# FirebeetleNodoFinal.net
KiCad netlist of a schematic drawn in Altium Designer
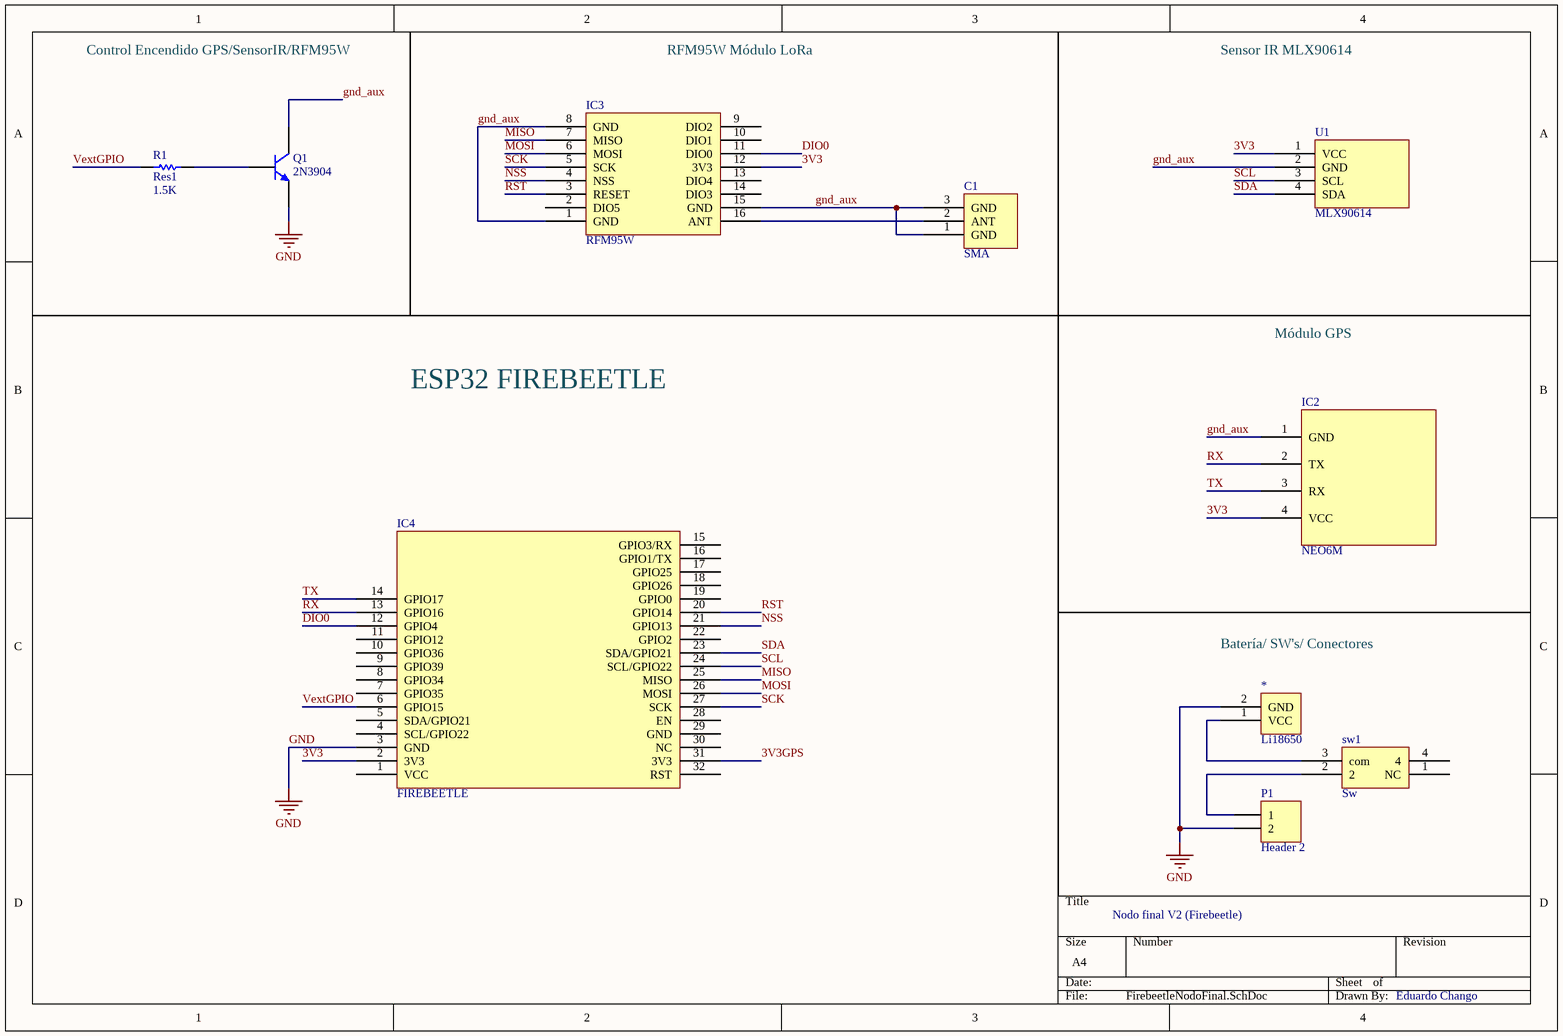
[diagram p0: FirebeetleNodoFinal.SchDoc]

(export (version "E")
  (design (tool "Eeschema 10.0.6"))
  (components
    (comp (ref "*")
      (value "Li18650")
      (footprint "Li18650")
      (libsource (lib "ComponentesTesis") (part "Li18650"))
    )
    (comp (ref "C1") (value "SMA") (footprint "SMA") (libsource (lib "ComponentesTesis") (part "SMA")))
    (comp (ref "IC2")
      (value "NEO6M")
      (footprint "NEO6M")
      (description "GPS NEO6M")
      (libsource (lib "ComponentesTesis") (part "NEO6M"))
    )
    (comp (ref "IC3")
      (value "RFM95W")
      (footprint "RFM95W")
      (libsource (lib "ComponentesTesis") (part "RFM95W"))
    )
    (comp (ref "IC4")
      (value "FIREBEETLE")
      (footprint "FIREBEETLE")
      (libsource (lib "ComponentesTesis") (part "FIREBEETLE"))
    )
    (comp (ref "P1")
      (value "Header 2")
      (footprint "HDR1X2")
      (description "Header, 2-Pin")
      (fields (field (name "PUBLISHER") "Altium Limited"))
      (libsource (lib "Miscellaneous Connectors") (part "Header 2"))
    )
    (comp (ref "Q1")
      (value "2N3904")
      (footprint "TO-92A")
      (description "NPN General Purpose Amplifier")
      (fields (field (name "PUBLISHER") "Altium Limited"))
      (libsource (lib "Miscellaneous Devices") (part "2N3904"))
    )
    (comp (ref "R1")
      (value "Res1")
      (footprint "AXIAL-0.3")
      (description "Resistor")
      (fields (field (name "ALTIUM_VALUE") "1.5K") (field (name "PUBLISHER") "Altium Limited"))
      (libsource (lib "Miscellaneous Devices") (part "Res1"))
    )
    (comp (ref "sw1")
      (value "Sw")
      (footprint "InterruptorSMD")
      (libsource (lib "ComponentesTesis") (part "Sw"))
    )
    (comp (ref "U1")
      (value "MLX90614")
      (footprint "IRSENSOR")
      (description "iR SENSOR TEMPERATURA")
      (libsource (lib "ComponentesTesis") (part "MLX90614"))
    )
  )
  (nets
    (net (code "1") (name "/3V3") (class "Default")
      (node (ref "IC2") (pin "4") (pinfunction "VCC_4") (pintype "passive"))
      (node (ref "IC3") (pin "12") (pinfunction "3V3_12") (pintype "power_in"))
      (node (ref "IC4") (pin "2") (pinfunction "3V3_2") (pintype "power_in"))
      (node (ref "U1") (pin "1") (pinfunction "VCC_1") (pintype "power_in"))
    )
    (net (code "2") (name "/3V3GPS") (class "Default")
      (node (ref "IC4") (pin "31") (pinfunction "3V3_31") (pintype "power_in"))
    )
    (net (code "3") (name "/DIO0") (class "Default")
      (node (ref "IC3") (pin "11") (pinfunction "DIO0_11") (pintype "passive"))
      (node (ref "IC4") (pin "12") (pinfunction "GPIO4_12") (pintype "power_in"))
    )
    (net (code "4") (name "/MISO") (class "Default")
      (node (ref "IC3") (pin "7") (pinfunction "MISO_7") (pintype "passive"))
      (node (ref "IC4") (pin "25") (pinfunction "MISO_25") (pintype "power_in"))
    )
    (net (code "5") (name "/MOSI") (class "Default")
      (node (ref "IC3") (pin "6") (pinfunction "MOSI_6") (pintype "passive"))
      (node (ref "IC4") (pin "26") (pinfunction "MOSI_26") (pintype "power_in"))
    )
    (net (code "6") (name "/NSS") (class "Default")
      (node (ref "IC3") (pin "4") (pinfunction "NSS_4") (pintype "passive"))
      (node (ref "IC4") (pin "21") (pinfunction "GPIO13_21") (pintype "power_in"))
    )
    (net (code "7") (name "/RST") (class "Default")
      (node (ref "IC3") (pin "3") (pinfunction "RESET_3") (pintype "passive"))
      (node (ref "IC4") (pin "20") (pinfunction "GPIO14_20") (pintype "power_in"))
    )
    (net (code "8") (name "/RX") (class "Default")
      (node (ref "IC2") (pin "2") (pinfunction "TX_2") (pintype "passive"))
      (node (ref "IC4") (pin "13") (pinfunction "GPIO16_13") (pintype "power_in"))
    )
    (net (code "9") (name "/SCK") (class "Default")
      (node (ref "IC3") (pin "5") (pinfunction "SCK_5") (pintype "passive"))
      (node (ref "IC4") (pin "27") (pinfunction "SCK_27") (pintype "power_in"))
    )
    (net (code "10") (name "/SCL") (class "Default")
      (node (ref "IC4") (pin "24") (pinfunction "SCL/GPIO22_24") (pintype "power_in"))
      (node (ref "U1") (pin "3") (pinfunction "SCL_3") (pintype "passive"))
    )
    (net (code "11") (name "/SDA") (class "Default")
      (node (ref "IC4") (pin "23") (pinfunction "SDA/GPIO21_23") (pintype "power_in"))
      (node (ref "U1") (pin "4") (pinfunction "SDA_4") (pintype "passive"))
    )
    (net (code "12") (name "/TX") (class "Default")
      (node (ref "IC2") (pin "3") (pinfunction "RX_3") (pintype "passive"))
      (node (ref "IC4") (pin "14") (pinfunction "GPIO17_14") (pintype "power_in"))
    )
    (net (code "13") (name "/VextGPIO") (class "Default")
      (node (ref "IC4") (pin "6") (pinfunction "GPIO15_6") (pintype "power_in"))
      (node (ref "R1") (pin "2") (pinfunction "2_2") (pintype "passive"))
    )
    (net (code "14") (name "/gnd_aux") (class "Default")
      (node (ref "C1") (pin "1") (pinfunction "GND_1") (pintype "passive"))
      (node (ref "C1") (pin "3") (pinfunction "GND_3") (pintype "passive"))
      (node (ref "IC2") (pin "1") (pinfunction "GND_1") (pintype "power_in"))
      (node (ref "IC3") (pin "1") (pinfunction "GND_1") (pintype "power_in"))
      (node (ref "IC3") (pin "15") (pinfunction "GND_15") (pintype "power_in"))
      (node (ref "IC3") (pin "8") (pinfunction "GND_8") (pintype "power_in"))
      (node (ref "Q1") (pin "3") (pinfunction "C_3") (pintype "passive"))
      (node (ref "U1") (pin "2") (pinfunction "GND_2") (pintype "power_in"))
    )
    (net (code "15") (name "GND") (class "Default")
      (node (ref "*") (pin "2") (pinfunction "GND_2") (pintype "passive"))
      (node (ref "IC4") (pin "3") (pinfunction "GND_3") (pintype "power_in"))
      (node (ref "P1") (pin "2") (pinfunction "2_2") (pintype "passive"))
      (node (ref "Q1") (pin "1") (pinfunction "E_1") (pintype "passive"))
    )
    (net (code "16") (name "Net-(*-VCC)") (class "Default")
      (node (ref "*") (pin "1") (pinfunction "VCC_1") (pintype "power_in"))
      (node (ref "sw1") (pin "3") (pinfunction "com_3") (pintype "passive"))
    )
    (net (code "17") (name "Net-(C1-ANT)") (class "Default")
      (node (ref "C1") (pin "2") (pinfunction "ANT_2") (pintype "passive"))
      (node (ref "IC3") (pin "16") (pinfunction "ANT_16") (pintype "passive"))
    )
    (net (code "18") (name "Net-(P1-Pad1)") (class "Default")
      (node (ref "P1") (pin "1") (pinfunction "1_1") (pintype "passive"))
      (node (ref "sw1") (pin "2") (pinfunction "2_2") (pintype "passive"))
    )
    (net (code "19") (name "Net-(Q1-B)") (class "Default")
      (node (ref "Q1") (pin "2") (pinfunction "B_2") (pintype "passive"))
      (node (ref "R1") (pin "1") (pinfunction "1_1") (pintype "passive"))
    )
    (net (code "20") (name "unconnected-(IC3-DIO1-Pad10)") (class "Default")
      (node (ref "IC3") (pin "10") (pinfunction "DIO1_10") (pintype "passive"))
    )
    (net (code "21") (name "unconnected-(IC3-DIO2-Pad9)") (class "Default")
      (node (ref "IC3") (pin "9") (pinfunction "DIO2_9") (pintype "passive"))
    )
    (net (code "22") (name "unconnected-(IC3-DIO3-Pad14)") (class "Default")
      (node (ref "IC3") (pin "14") (pinfunction "DIO3_14") (pintype "passive"))
    )
    (net (code "23") (name "unconnected-(IC3-DIO4-Pad13)") (class "Default")
      (node (ref "IC3") (pin "13") (pinfunction "DIO4_13") (pintype "passive"))
    )
    (net (code "24") (name "unconnected-(IC3-DIO5-Pad2)") (class "Default")
      (node (ref "IC3") (pin "2") (pinfunction "DIO5_2") (pintype "passive"))
    )
    (net (code "25") (name "unconnected-(IC4-EN-Pad28)") (class "Default")
      (node (ref "IC4") (pin "28") (pinfunction "EN_28") (pintype "power_in"))
    )
    (net (code "26") (name "unconnected-(IC4-GND-Pad29)") (class "Default")
      (node (ref "IC4") (pin "29") (pinfunction "GND_29") (pintype "power_in"))
    )
    (net (code "27") (name "unconnected-(IC4-GPIO0-Pad19)") (class "Default")
      (node (ref "IC4") (pin "19") (pinfunction "GPIO0_19") (pintype "power_in"))
    )
    (net (code "28") (name "unconnected-(IC4-GPIO1{slash}TX-Pad16)") (class "Default")
      (node (ref "IC4") (pin "16") (pinfunction "GPIO1/TX_16") (pintype "power_in"))
    )
    (net (code "29") (name "unconnected-(IC4-GPIO2-Pad22)") (class "Default")
      (node (ref "IC4") (pin "22") (pinfunction "GPIO2_22") (pintype "power_in"))
    )
    (net (code "30") (name "unconnected-(IC4-GPIO3{slash}RX-Pad15)") (class "Default")
      (node (ref "IC4") (pin "15") (pinfunction "GPIO3/RX_15") (pintype "power_in"))
    )
    (net (code "31") (name "unconnected-(IC4-GPIO12-Pad11)") (class "Default")
      (node (ref "IC4") (pin "11") (pinfunction "GPIO12_11") (pintype "power_in"))
    )
    (net (code "32") (name "unconnected-(IC4-GPIO25-Pad17)") (class "Default")
      (node (ref "IC4") (pin "17") (pinfunction "GPIO25_17") (pintype "power_in"))
    )
    (net (code "33") (name "unconnected-(IC4-GPIO26-Pad18)") (class "Default")
      (node (ref "IC4") (pin "18") (pinfunction "GPIO26_18") (pintype "power_in"))
    )
    (net (code "34") (name "unconnected-(IC4-GPIO34-Pad8)") (class "Default")
      (node (ref "IC4") (pin "8") (pinfunction "GPIO34_8") (pintype "power_in"))
    )
    (net (code "35") (name "unconnected-(IC4-GPIO35-Pad7)") (class "Default")
      (node (ref "IC4") (pin "7") (pinfunction "GPIO35_7") (pintype "power_in"))
    )
    (net (code "36") (name "unconnected-(IC4-GPIO36-Pad10)") (class "Default")
      (node (ref "IC4") (pin "10") (pinfunction "GPIO36_10") (pintype "power_in"))
    )
    (net (code "37") (name "unconnected-(IC4-GPIO39-Pad9)") (class "Default")
      (node (ref "IC4") (pin "9") (pinfunction "GPIO39_9") (pintype "power_in"))
    )
    (net (code "38") (name "unconnected-(IC4-NC-Pad30)") (class "Default")
      (node (ref "IC4") (pin "30") (pinfunction "NC_30") (pintype "power_in"))
    )
    (net (code "39") (name "unconnected-(IC4-RST-Pad32)") (class "Default")
      (node (ref "IC4") (pin "32") (pinfunction "RST_32") (pintype "power_in"))
    )
    (net (code "40") (name "unconnected-(IC4-SCL{slash}GPIO22-Pad4)") (class "Default")
      (node (ref "IC4") (pin "4") (pinfunction "SCL/GPIO22_4") (pintype "power_in"))
    )
    (net (code "41") (name "unconnected-(IC4-SDA{slash}GPIO21-Pad5)") (class "Default")
      (node (ref "IC4") (pin "5") (pinfunction "SDA/GPIO21_5") (pintype "power_in"))
    )
    (net (code "42") (name "unconnected-(IC4-VCC-Pad1)") (class "Default")
      (node (ref "IC4") (pin "1") (pinfunction "VCC_1") (pintype "power_in"))
    )
    (net (code "43") (name "unconnected-(sw1-NC-Pad1)") (class "Default")
      (node (ref "sw1") (pin "1") (pinfunction "NC_1") (pintype "passive"))
    )
    (net (code "44") (name "unconnected-(sw1-Pad4)") (class "Default")
      (node (ref "sw1") (pin "4") (pinfunction "4_4") (pintype "passive"))
    )
  )
)
